# 1_Main.net
KiCad netlist of a schematic drawn in EAGLE
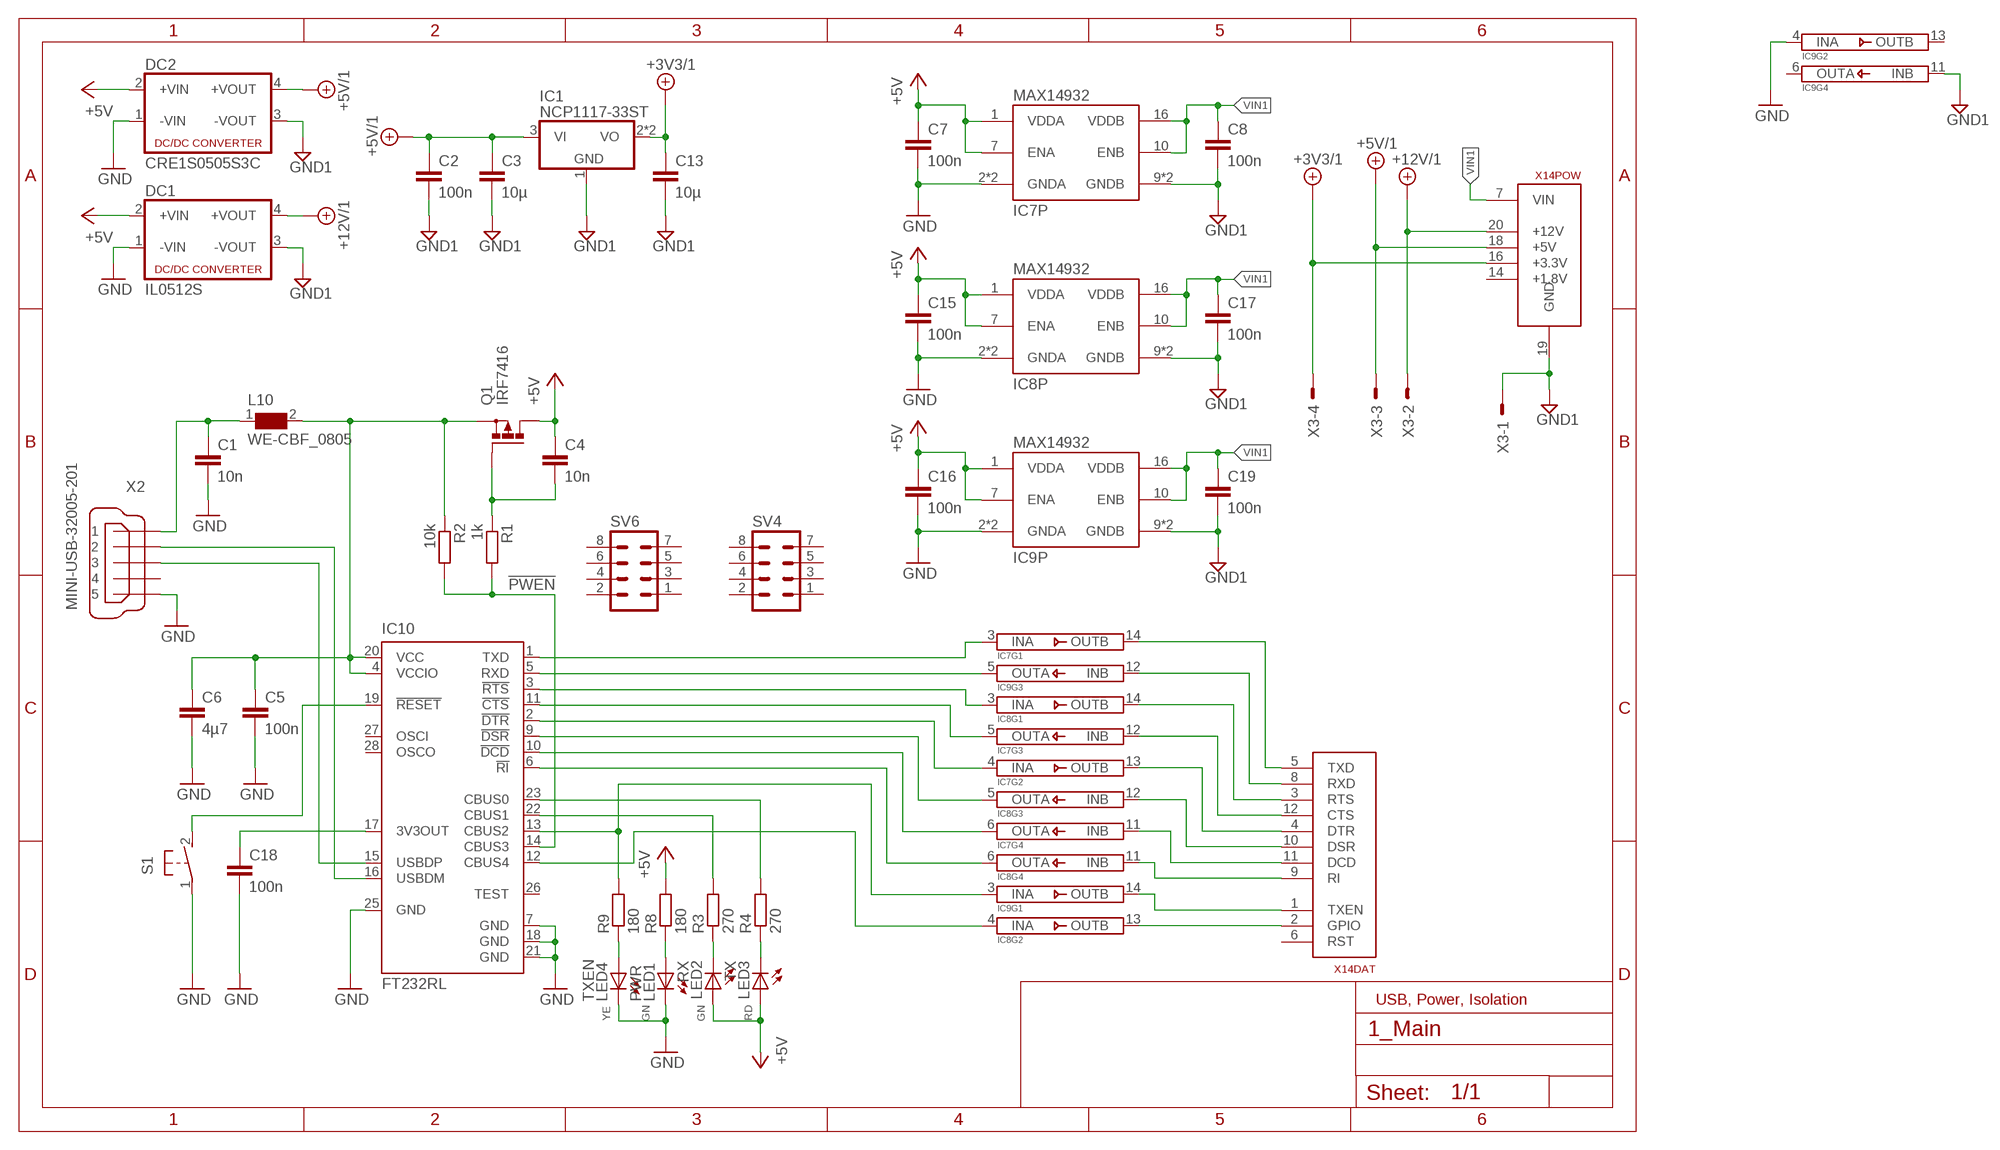
[diagram p0: schematic, sheet 1]

(export (version "E")
  (design (tool "Eeschema 10.0.6"))
  (components
    (comp (ref "C1")
      (value "10n")
      (footprint "eagle-import:C0805")
      (libsource (lib "eagle-import") (part "C-EUC0805"))
    )
    (comp (ref "C2")
      (value "100n")
      (footprint "eagle-import:C0805")
      (libsource (lib "eagle-import") (part "C-EUC0805"))
    )
    (comp (ref "C3")
      (value "10µ")
      (footprint "eagle-import:C0805")
      (libsource (lib "eagle-import") (part "C-EUC0805"))
    )
    (comp (ref "C4")
      (value "10n")
      (footprint "eagle-import:C0805")
      (libsource (lib "eagle-import") (part "C-EUC0805"))
    )
    (comp (ref "C5")
      (value "100n")
      (footprint "eagle-import:C0805")
      (libsource (lib "eagle-import") (part "C-EUC0805"))
    )
    (comp (ref "C6")
      (value "4µ7")
      (footprint "eagle-import:C0805")
      (libsource (lib "eagle-import") (part "C-EUC0805"))
    )
    (comp (ref "C7")
      (value "100n")
      (footprint "eagle-import:C0805")
      (libsource (lib "eagle-import") (part "C-EUC0805"))
    )
    (comp (ref "C8")
      (value "100n")
      (footprint "eagle-import:C0805")
      (libsource (lib "eagle-import") (part "C-EUC0805"))
    )
    (comp (ref "C13")
      (value "10µ")
      (footprint "eagle-import:C0805")
      (libsource (lib "eagle-import") (part "C-EUC0805"))
    )
    (comp (ref "C15")
      (value "100n")
      (footprint "eagle-import:C0805")
      (libsource (lib "eagle-import") (part "C-EUC0805"))
    )
    (comp (ref "C16")
      (value "100n")
      (footprint "eagle-import:C0805")
      (libsource (lib "eagle-import") (part "C-EUC0805"))
    )
    (comp (ref "C17")
      (value "100n")
      (footprint "eagle-import:C0805")
      (libsource (lib "eagle-import") (part "C-EUC0805"))
    )
    (comp (ref "C18")
      (value "100n")
      (footprint "eagle-import:C0805")
      (libsource (lib "eagle-import") (part "C-EUC0805"))
    )
    (comp (ref "C19")
      (value "100n")
      (footprint "eagle-import:C0805")
      (libsource (lib "eagle-import") (part "C-EUC0805"))
    )
    (comp (ref "DC1")
      (value "IL0512S")
      (footprint "eagle-import:NME")
      (fields (field (name "MF") "C & D TECHNOLOGIES, INC") (field (name "MPN") "NME1205D"))
      (libsource (lib "eagle-import") (part "NME"))
    )
    (comp (ref "DC2")
      (value "CRE1S0505S3C")
      (footprint "eagle-import:NME")
      (fields (field (name "MF") "C & D TECHNOLOGIES, INC") (field (name "MPN") "NME1205D"))
      (libsource (lib "eagle-import") (part "NME"))
    )
    (comp (ref "IC1")
      (value "NCP1117-33ST")
      (footprint "eagle-import:SOT223")
      (libsource (lib "eagle-import") (part "NCP1117ST-33"))
    )
    (comp (ref "IC7")
      (value "MAX14932")
      (footprint "eagle-import:SO16")
      (libsource (lib "eagle-import") (part "MAX14932"))
    )
    (comp (ref "IC8")
      (value "MAX14932")
      (footprint "eagle-import:SO16")
      (libsource (lib "eagle-import") (part "MAX14932"))
    )
    (comp (ref "IC9")
      (value "MAX14932")
      (footprint "eagle-import:SO16")
      (libsource (lib "eagle-import") (part "MAX14932"))
    )
    (comp (ref "IC10")
      (value "FT232RL")
      (footprint "eagle-import:SSOP28")
      (libsource (lib "eagle-import") (part "FT232RL"))
    )
    (comp (ref "L10")
      (value "WE-CBF_0805")
      (footprint "eagle-import:0805")
      (libsource (lib "eagle-import") (part "WE-CBF_0805"))
    )
    (comp (ref "LED1")
      (value "PWR")
      (footprint "eagle-import:CHIPLED_0603")
      (fields (field (name "COLOR") "GN"))
      (libsource (lib "eagle-import") (part "LEDCHIPLED_0603"))
    )
    (comp (ref "LED2")
      (value "RX")
      (footprint "eagle-import:CHIPLED_0603")
      (fields (field (name "COLOR") "GN"))
      (libsource (lib "eagle-import") (part "LEDCHIPLED_0603"))
    )
    (comp (ref "LED3")
      (value "TX")
      (footprint "eagle-import:CHIPLED_0603")
      (fields (field (name "COLOR") "RD"))
      (libsource (lib "eagle-import") (part "LEDCHIPLED_0603"))
    )
    (comp (ref "LED4")
      (value "TXEN")
      (footprint "eagle-import:CHIPLED_0603")
      (fields (field (name "COLOR") "YE"))
      (libsource (lib "eagle-import") (part "LEDCHIPLED_0603"))
    )
    (comp (ref "Q1")
      (value "IRF7416")
      (footprint "eagle-import:SO-08")
      (libsource (lib "eagle-import") (part "P-MOSFET-SO8"))
    )
    (comp (ref "R1")
      (value "1k")
      (footprint "eagle-import:R0805")
      (libsource (lib "eagle-import") (part "R-EU_R0805"))
    )
    (comp (ref "R2")
      (value "10k")
      (footprint "eagle-import:R0805")
      (libsource (lib "eagle-import") (part "R-EU_R0805"))
    )
    (comp (ref "R3")
      (value "270")
      (footprint "eagle-import:R0805")
      (libsource (lib "eagle-import") (part "R-EU_R0805"))
    )
    (comp (ref "R4")
      (value "270")
      (footprint "eagle-import:R0805")
      (libsource (lib "eagle-import") (part "R-EU_R0805"))
    )
    (comp (ref "R8")
      (value "180")
      (footprint "eagle-import:R0805")
      (libsource (lib "eagle-import") (part "R-EU_R0805"))
    )
    (comp (ref "R9")
      (value "180")
      (footprint "eagle-import:R0805")
      (libsource (lib "eagle-import") (part "R-EU_R0805"))
    )
    (comp (ref "S1")
      (value "31-XX")
      (footprint "eagle-import:B3F-31XX")
      (fields (field (name "MPN") "B3F-3100"))
      (libsource (lib "eagle-import") (part "31-XX"))
    )
    (comp (ref "SV4")
      (value "MA04-2")
      (footprint "eagle-import:MA04-2")
      (libsource (lib "eagle-import") (part "MA04-2"))
    )
    (comp (ref "SV6")
      (value "MA04-2")
      (footprint "eagle-import:MA04-2")
      (libsource (lib "eagle-import") (part "MA04-2"))
    )
    (comp (ref "X2")
      (value "MINI-USB-32005-201")
      (footprint "eagle-import:32005-201")
      (libsource (lib "eagle-import") (part "MINI-USB-32005-201"))
    )
    (comp (ref "X3")
      (value "AKL18X-04W")
      (footprint "eagle-import:AKL182-04")
      (libsource (lib "eagle-import") (part "AKL18X-04W"))
    )
    (comp (ref "X14")
      (value "ALLSERIALMM")
      (footprint "eagle-import:MAIN-THT")
      (libsource (lib "eagle-import") (part "ALLSERIALMM"))
    )
  )
  (nets
    (net (code "1") (name "+3V3{slash}1") (class "Default")
      (node (ref "C13") (pin "1") (pinfunction "1_1") (pintype "passive"))
      (node (ref "IC1") (pin "2") (pinfunction "VO_2") (pintype "passive"))
      (node (ref "IC1") (pin "4") (pinfunction "VO_4") (pintype "passive"))
      (node (ref "X14") (pin "16") (pinfunction "+3.3V_16") (pintype "bidirectional"))
      (node (ref "X3") (pin "P$4") (pinfunction "S_P$4") (pintype "passive"))
    )
    (net (code "2") (name "+5V") (class "Default")
      (node (ref "C15") (pin "1") (pinfunction "1_1") (pintype "passive"))
      (node (ref "C16") (pin "1") (pinfunction "1_1") (pintype "passive"))
      (node (ref "C4") (pin "1") (pinfunction "1_1") (pintype "passive"))
      (node (ref "C7") (pin "1") (pinfunction "1_1") (pintype "passive"))
      (node (ref "DC1") (pin "2") (pinfunction "+VIN_2") (pintype "passive"))
      (node (ref "DC2") (pin "2") (pinfunction "+VIN_2") (pintype "passive"))
      (node (ref "IC7") (pin "1") (pinfunction "VDDA_1") (pintype "power_in"))
      (node (ref "IC7") (pin "7") (pinfunction "ENA_7") (pintype "input"))
      (node (ref "IC8") (pin "1") (pinfunction "VDDA_1") (pintype "power_in"))
      (node (ref "IC8") (pin "7") (pinfunction "ENA_7") (pintype "input"))
      (node (ref "IC9") (pin "1") (pinfunction "VDDA_1") (pintype "power_in"))
      (node (ref "IC9") (pin "7") (pinfunction "ENA_7") (pintype "input"))
      (node (ref "LED2") (pin "A") (pinfunction "A_A") (pintype "passive"))
      (node (ref "LED3") (pin "A") (pinfunction "A_A") (pintype "passive"))
      (node (ref "Q1") (pin "5") (pinfunction "D_5") (pintype "passive"))
      (node (ref "Q1") (pin "6") (pinfunction "D_6") (pintype "passive"))
      (node (ref "Q1") (pin "7") (pinfunction "D_7") (pintype "passive"))
      (node (ref "Q1") (pin "8") (pinfunction "D_8") (pintype "passive"))
      (node (ref "R8") (pin "2") (pinfunction "2_2") (pintype "passive"))
    )
    (net (code "3") (name "+5V{slash}1") (class "Default")
      (node (ref "C2") (pin "1") (pinfunction "1_1") (pintype "passive"))
      (node (ref "C3") (pin "1") (pinfunction "1_1") (pintype "passive"))
      (node (ref "DC2") (pin "4") (pinfunction "+VOUT_4") (pintype "passive"))
      (node (ref "IC1") (pin "3") (pinfunction "VI_3") (pintype "input"))
      (node (ref "X14") (pin "18") (pinfunction "+5V_18") (pintype "bidirectional"))
      (node (ref "X3") (pin "P$3") (pinfunction "S_P$3") (pintype "passive"))
    )
    (net (code "4") (name "+12V{slash}1") (class "Default")
      (node (ref "DC1") (pin "4") (pinfunction "+VOUT_4") (pintype "passive"))
      (node (ref "X14") (pin "20") (pinfunction "+12V_20") (pintype "bidirectional"))
      (node (ref "X3") (pin "P$2") (pinfunction "S_P$2") (pintype "passive"))
    )
    (net (code "5") (name "/~{PWEN}") (class "Default")
      (node (ref "IC10") (pin "14") (pinfunction "CBUS3_14") (pintype "bidirectional"))
      (node (ref "R1") (pin "2") (pinfunction "2_2") (pintype "passive"))
      (node (ref "R2") (pin "2") (pinfunction "2_2") (pintype "passive"))
    )
    (net (code "6") (name "GND") (class "Default")
      (node (ref "C1") (pin "2") (pinfunction "2_2") (pintype "passive"))
      (node (ref "C15") (pin "2") (pinfunction "2_2") (pintype "passive"))
      (node (ref "C16") (pin "2") (pinfunction "2_2") (pintype "passive"))
      (node (ref "C18") (pin "2") (pinfunction "2_2") (pintype "passive"))
      (node (ref "C5") (pin "2") (pinfunction "2_2") (pintype "passive"))
      (node (ref "C6") (pin "2") (pinfunction "2_2") (pintype "passive"))
      (node (ref "C7") (pin "2") (pinfunction "2_2") (pintype "passive"))
      (node (ref "DC1") (pin "1") (pinfunction "-VIN_1") (pintype "passive"))
      (node (ref "DC2") (pin "1") (pinfunction "-VIN_1") (pintype "passive"))
      (node (ref "IC10") (pin "18") (pinfunction "GND_18") (pintype "power_in"))
      (node (ref "IC10") (pin "21") (pinfunction "GND_21") (pintype "power_in"))
      (node (ref "IC10") (pin "25") (pinfunction "GND_25") (pintype "power_in"))
      (node (ref "IC10") (pin "7") (pinfunction "GND_7") (pintype "power_in"))
      (node (ref "IC7") (pin "2") (pinfunction "GNDA_2") (pintype "power_in"))
      (node (ref "IC7") (pin "8") (pinfunction "GNDA_8") (pintype "power_in"))
      (node (ref "IC8") (pin "2") (pinfunction "GNDA_2") (pintype "power_in"))
      (node (ref "IC8") (pin "8") (pinfunction "GNDA_8") (pintype "power_in"))
      (node (ref "IC9") (pin "2") (pinfunction "GNDA_2") (pintype "power_in"))
      (node (ref "IC9") (pin "4") (pinfunction "INA_4") (pintype "input"))
      (node (ref "IC9") (pin "8") (pinfunction "GNDA_8") (pintype "power_in"))
      (node (ref "LED1") (pin "C") (pinfunction "C_C") (pintype "passive"))
      (node (ref "LED4") (pin "C") (pinfunction "C_C") (pintype "passive"))
      (node (ref "S1") (pin "1") (pinfunction "P_1") (pintype "passive"))
      (node (ref "X2") (pin "5") (pinfunction "5_5") (pintype "passive"))
    )
    (net (code "7") (name "GND1") (class "Default")
      (node (ref "C13") (pin "2") (pinfunction "2_2") (pintype "passive"))
      (node (ref "C17") (pin "2") (pinfunction "2_2") (pintype "passive"))
      (node (ref "C19") (pin "2") (pinfunction "2_2") (pintype "passive"))
      (node (ref "C2") (pin "2") (pinfunction "2_2") (pintype "passive"))
      (node (ref "C3") (pin "2") (pinfunction "2_2") (pintype "passive"))
      (node (ref "C8") (pin "2") (pinfunction "2_2") (pintype "passive"))
      (node (ref "DC1") (pin "3") (pinfunction "-VOUT_3") (pintype "passive"))
      (node (ref "DC2") (pin "3") (pinfunction "-VOUT_3") (pintype "passive"))
      (node (ref "IC1") (pin "1") (pinfunction "GND_1") (pintype "passive"))
      (node (ref "IC7") (pin "15") (pinfunction "GNDB_15") (pintype "power_in"))
      (node (ref "IC7") (pin "9") (pinfunction "GNDB_9") (pintype "power_in"))
      (node (ref "IC8") (pin "15") (pinfunction "GNDB_15") (pintype "power_in"))
      (node (ref "IC8") (pin "9") (pinfunction "GNDB_9") (pintype "power_in"))
      (node (ref "IC9") (pin "11") (pinfunction "INB_11") (pintype "input"))
      (node (ref "IC9") (pin "15") (pinfunction "GNDB_15") (pintype "power_in"))
      (node (ref "IC9") (pin "9") (pinfunction "GNDB_9") (pintype "power_in"))
      (node (ref "X14") (pin "19") (pinfunction "GND_19") (pintype "bidirectional"))
      (node (ref "X3") (pin "P$1") (pinfunction "S_P$1") (pintype "passive"))
    )
    (net (code "8") (name "Net-(C1-Pad1)") (class "Default")
      (node (ref "C1") (pin "1") (pinfunction "1_1") (pintype "passive"))
      (node (ref "L10") (pin "1") (pinfunction "1_1") (pintype "passive"))
      (node (ref "X2") (pin "1") (pinfunction "1_1") (pintype "passive"))
    )
    (net (code "9") (name "Net-(IC7A-OUTB)") (class "Default")
      (node (ref "IC7") (pin "14") (pinfunction "OUTB_14") (pintype "output"))
      (node (ref "X14") (pin "5") (pinfunction "TXD_5") (pintype "bidirectional"))
    )
    (net (code "10") (name "Net-(IC7B-OUTB)") (class "Default")
      (node (ref "IC7") (pin "13") (pinfunction "OUTB_13") (pintype "output"))
      (node (ref "X14") (pin "4") (pinfunction "DTR_4") (pintype "bidirectional"))
    )
    (net (code "11") (name "Net-(IC7C-INB)") (class "Default")
      (node (ref "IC7") (pin "12") (pinfunction "INB_12") (pintype "input"))
      (node (ref "X14") (pin "12") (pinfunction "CTS_12") (pintype "bidirectional"))
    )
    (net (code "12") (name "Net-(IC7D-INB)") (class "Default")
      (node (ref "IC7") (pin "11") (pinfunction "INB_11") (pintype "input"))
      (node (ref "X14") (pin "11") (pinfunction "DCD_11") (pintype "bidirectional"))
    )
    (net (code "13") (name "Net-(IC8A-OUTB)") (class "Default")
      (node (ref "IC8") (pin "14") (pinfunction "OUTB_14") (pintype "output"))
      (node (ref "X14") (pin "3") (pinfunction "RTS_3") (pintype "bidirectional"))
    )
    (net (code "14") (name "Net-(IC8B-OUTB)") (class "Default")
      (node (ref "IC8") (pin "13") (pinfunction "OUTB_13") (pintype "output"))
      (node (ref "X14") (pin "2") (pinfunction "GPIO_2") (pintype "bidirectional"))
    )
    (net (code "15") (name "Net-(IC8C-INB)") (class "Default")
      (node (ref "IC8") (pin "12") (pinfunction "INB_12") (pintype "input"))
      (node (ref "X14") (pin "10") (pinfunction "DSR_10") (pintype "bidirectional"))
    )
    (net (code "16") (name "Net-(IC8D-INB)") (class "Default")
      (node (ref "IC8") (pin "11") (pinfunction "INB_11") (pintype "input"))
      (node (ref "X14") (pin "9") (pinfunction "RI_9") (pintype "bidirectional"))
    )
    (net (code "17") (name "Net-(IC9A-OUTB)") (class "Default")
      (node (ref "IC9") (pin "14") (pinfunction "OUTB_14") (pintype "output"))
      (node (ref "X14") (pin "1") (pinfunction "TXEN_1") (pintype "bidirectional"))
    )
    (net (code "18") (name "Net-(IC9C-INB)") (class "Default")
      (node (ref "IC9") (pin "12") (pinfunction "INB_12") (pintype "input"))
      (node (ref "X14") (pin "8") (pinfunction "RXD_8") (pintype "bidirectional"))
    )
    (net (code "19") (name "Net-(IC10-3V3OUT)") (class "Default")
      (node (ref "C18") (pin "1") (pinfunction "1_1") (pintype "passive"))
      (node (ref "IC10") (pin "17") (pinfunction "3V3OUT_17") (pintype "output"))
    )
    (net (code "20") (name "Net-(IC10-CBUS0)") (class "Default")
      (node (ref "IC10") (pin "23") (pinfunction "CBUS0_23") (pintype "bidirectional"))
      (node (ref "R4") (pin "2") (pinfunction "2_2") (pintype "passive"))
    )
    (net (code "21") (name "Net-(IC10-CBUS1)") (class "Default")
      (node (ref "IC10") (pin "22") (pinfunction "CBUS1_22") (pintype "bidirectional"))
      (node (ref "R3") (pin "2") (pinfunction "2_2") (pintype "passive"))
    )
    (net (code "22") (name "Net-(IC10-CBUS2)") (class "Default")
      (node (ref "IC10") (pin "13") (pinfunction "CBUS2_13") (pintype "bidirectional"))
      (node (ref "IC9") (pin "3") (pinfunction "INA_3") (pintype "input"))
      (node (ref "R9") (pin "2") (pinfunction "2_2") (pintype "passive"))
    )
    (net (code "23") (name "Net-(IC10-CBUS4)") (class "Default")
      (node (ref "IC10") (pin "12") (pinfunction "CBUS4_12") (pintype "bidirectional"))
      (node (ref "IC8") (pin "4") (pinfunction "INA_4") (pintype "input"))
    )
    (net (code "24") (name "Net-(IC10-RXD)") (class "Default")
      (node (ref "IC10") (pin "5") (pinfunction "RXD_5") (pintype "input"))
      (node (ref "IC9") (pin "5") (pinfunction "OUTA_5") (pintype "output"))
    )
    (net (code "25") (name "Net-(IC10-TXD)") (class "Default")
      (node (ref "IC10") (pin "1") (pinfunction "TXD_1") (pintype "output"))
      (node (ref "IC7") (pin "3") (pinfunction "INA_3") (pintype "input"))
    )
    (net (code "26") (name "Net-(IC10-USBDM)") (class "Default")
      (node (ref "IC10") (pin "16") (pinfunction "USBDM_16") (pintype "bidirectional"))
      (node (ref "X2") (pin "2") (pinfunction "2_2") (pintype "passive"))
    )
    (net (code "27") (name "Net-(IC10-USBDP)") (class "Default")
      (node (ref "IC10") (pin "15") (pinfunction "USBDP_15") (pintype "bidirectional"))
      (node (ref "X2") (pin "3") (pinfunction "3_3") (pintype "passive"))
    )
    (net (code "28") (name "Net-(IC10-VCC)") (class "Default")
      (node (ref "C5") (pin "1") (pinfunction "1_1") (pintype "passive"))
      (node (ref "C6") (pin "1") (pinfunction "1_1") (pintype "passive"))
      (node (ref "IC10") (pin "20") (pinfunction "VCC_20") (pintype "power_in"))
      (node (ref "IC10") (pin "4") (pinfunction "VCCIO_4") (pintype "power_in"))
      (node (ref "L10") (pin "2") (pinfunction "2_2") (pintype "passive"))
      (node (ref "Q1") (pin "1") (pinfunction "S_1") (pintype "passive"))
      (node (ref "Q1") (pin "2") (pinfunction "S_2") (pintype "passive"))
      (node (ref "Q1") (pin "3") (pinfunction "S_3") (pintype "passive"))
      (node (ref "R2") (pin "1") (pinfunction "1_1") (pintype "passive"))
    )
    (net (code "29") (name "Net-(IC10-~{CTS})") (class "Default")
      (node (ref "IC10") (pin "11") (pinfunction "~{CTS}_11") (pintype "input"))
      (node (ref "IC7") (pin "5") (pinfunction "OUTA_5") (pintype "output"))
    )
    (net (code "30") (name "Net-(IC10-~{DCD})") (class "Default")
      (node (ref "IC10") (pin "10") (pinfunction "~{DCD}_10") (pintype "input"))
      (node (ref "IC7") (pin "6") (pinfunction "OUTA_6") (pintype "output"))
    )
    (net (code "31") (name "Net-(IC10-~{DSR})") (class "Default")
      (node (ref "IC10") (pin "9") (pinfunction "~{DSR}_9") (pintype "input"))
      (node (ref "IC8") (pin "5") (pinfunction "OUTA_5") (pintype "output"))
    )
    (net (code "32") (name "Net-(IC10-~{DTR})") (class "Default")
      (node (ref "IC10") (pin "2") (pinfunction "~{DTR}_2") (pintype "output"))
      (node (ref "IC7") (pin "4") (pinfunction "INA_4") (pintype "input"))
    )
    (net (code "33") (name "Net-(IC10-~{RESET})") (class "Default")
      (node (ref "IC10") (pin "19") (pinfunction "~{RESET}_19") (pintype "input"))
      (node (ref "S1") (pin "2") (pinfunction "S_2") (pintype "passive"))
    )
    (net (code "34") (name "Net-(IC10-~{RI})") (class "Default")
      (node (ref "IC10") (pin "6") (pinfunction "~{RI}_6") (pintype "input"))
      (node (ref "IC8") (pin "6") (pinfunction "OUTA_6") (pintype "output"))
    )
    (net (code "35") (name "Net-(IC10-~{RTS})") (class "Default")
      (node (ref "IC10") (pin "3") (pinfunction "~{RTS}_3") (pintype "output"))
      (node (ref "IC8") (pin "3") (pinfunction "INA_3") (pintype "input"))
    )
    (net (code "36") (name "Net-(LED1-PadA)") (class "Default")
      (node (ref "LED1") (pin "A") (pinfunction "A_A") (pintype "passive"))
      (node (ref "R8") (pin "1") (pinfunction "1_1") (pintype "passive"))
    )
    (net (code "37") (name "Net-(LED2-PadC)") (class "Default")
      (node (ref "LED2") (pin "C") (pinfunction "C_C") (pintype "passive"))
      (node (ref "R3") (pin "1") (pinfunction "1_1") (pintype "passive"))
    )
    (net (code "38") (name "Net-(LED3-PadC)") (class "Default")
      (node (ref "LED3") (pin "C") (pinfunction "C_C") (pintype "passive"))
      (node (ref "R4") (pin "1") (pinfunction "1_1") (pintype "passive"))
    )
    (net (code "39") (name "Net-(LED4-PadA)") (class "Default")
      (node (ref "LED4") (pin "A") (pinfunction "A_A") (pintype "passive"))
      (node (ref "R9") (pin "1") (pinfunction "1_1") (pintype "passive"))
    )
    (net (code "40") (name "Net-(Q1-G)") (class "Default")
      (node (ref "C4") (pin "2") (pinfunction "2_2") (pintype "passive"))
      (node (ref "Q1") (pin "4") (pinfunction "G_4") (pintype "passive"))
      (node (ref "R1") (pin "1") (pinfunction "1_1") (pintype "passive"))
    )
    (net (code "41") (name "VIN1") (class "Default")
      (node (ref "C17") (pin "1") (pinfunction "1_1") (pintype "passive"))
      (node (ref "C19") (pin "1") (pinfunction "1_1") (pintype "passive"))
      (node (ref "C8") (pin "1") (pinfunction "1_1") (pintype "passive"))
      (node (ref "IC7") (pin "10") (pinfunction "ENB_10") (pintype "input"))
      (node (ref "IC7") (pin "16") (pinfunction "VDDB_16") (pintype "power_in"))
      (node (ref "IC8") (pin "10") (pinfunction "ENB_10") (pintype "input"))
      (node (ref "IC8") (pin "16") (pinfunction "VDDB_16") (pintype "power_in"))
      (node (ref "IC9") (pin "10") (pinfunction "ENB_10") (pintype "input"))
      (node (ref "IC9") (pin "16") (pinfunction "VDDB_16") (pintype "power_in"))
      (node (ref "X14") (pin "7") (pinfunction "VIN_7") (pintype "bidirectional"))
    )
    (net (code "42") (name "unconnected-(IC9B-OUTB-Pad13)") (class "Default")
      (node (ref "IC9") (pin "13") (pinfunction "OUTB_13") (pintype "output"))
    )
    (net (code "43") (name "unconnected-(IC9D-OUTA-Pad6)") (class "Default")
      (node (ref "IC9") (pin "6") (pinfunction "OUTA_6") (pintype "output"))
    )
    (net (code "44") (name "unconnected-(IC10-OSCI-Pad27)") (class "Default")
      (node (ref "IC10") (pin "27") (pinfunction "OSCI_27") (pintype "input"))
    )
    (net (code "45") (name "unconnected-(IC10-OSCO-Pad28)") (class "Default")
      (node (ref "IC10") (pin "28") (pinfunction "OSCO_28") (pintype "output"))
    )
    (net (code "46") (name "unconnected-(IC10-TEST-Pad26)") (class "Default")
      (node (ref "IC10") (pin "26") (pinfunction "TEST_26") (pintype "input"))
    )
    (net (code "47") (name "unconnected-(SV4-Pad1)") (class "Default")
      (node (ref "SV4") (pin "1") (pinfunction "1_1") (pintype "passive"))
    )
    (net (code "48") (name "unconnected-(SV4-Pad2)") (class "Default")
      (node (ref "SV4") (pin "2") (pinfunction "2_2") (pintype "passive"))
    )
    (net (code "49") (name "unconnected-(SV4-Pad3)") (class "Default")
      (node (ref "SV4") (pin "3") (pinfunction "3_3") (pintype "passive"))
    )
    (net (code "50") (name "unconnected-(SV4-Pad4)") (class "Default")
      (node (ref "SV4") (pin "4") (pinfunction "4_4") (pintype "passive"))
    )
    (net (code "51") (name "unconnected-(SV4-Pad5)") (class "Default")
      (node (ref "SV4") (pin "5") (pinfunction "5_5") (pintype "passive"))
    )
    (net (code "52") (name "unconnected-(SV4-Pad6)") (class "Default")
      (node (ref "SV4") (pin "6") (pinfunction "6_6") (pintype "passive"))
    )
    (net (code "53") (name "unconnected-(SV4-Pad7)") (class "Default")
      (node (ref "SV4") (pin "7") (pinfunction "7_7") (pintype "passive"))
    )
    (net (code "54") (name "unconnected-(SV4-Pad8)") (class "Default")
      (node (ref "SV4") (pin "8") (pinfunction "8_8") (pintype "passive"))
    )
    (net (code "55") (name "unconnected-(SV6-Pad1)") (class "Default")
      (node (ref "SV6") (pin "1") (pinfunction "1_1") (pintype "passive"))
    )
    (net (code "56") (name "unconnected-(SV6-Pad2)") (class "Default")
      (node (ref "SV6") (pin "2") (pinfunction "2_2") (pintype "passive"))
    )
    (net (code "57") (name "unconnected-(SV6-Pad3)") (class "Default")
      (node (ref "SV6") (pin "3") (pinfunction "3_3") (pintype "passive"))
    )
    (net (code "58") (name "unconnected-(SV6-Pad4)") (class "Default")
      (node (ref "SV6") (pin "4") (pinfunction "4_4") (pintype "passive"))
    )
    (net (code "59") (name "unconnected-(SV6-Pad5)") (class "Default")
      (node (ref "SV6") (pin "5") (pinfunction "5_5") (pintype "passive"))
    )
    (net (code "60") (name "unconnected-(SV6-Pad6)") (class "Default")
      (node (ref "SV6") (pin "6") (pinfunction "6_6") (pintype "passive"))
    )
    (net (code "61") (name "unconnected-(SV6-Pad7)") (class "Default")
      (node (ref "SV6") (pin "7") (pinfunction "7_7") (pintype "passive"))
    )
    (net (code "62") (name "unconnected-(SV6-Pad8)") (class "Default")
      (node (ref "SV6") (pin "8") (pinfunction "8_8") (pintype "passive"))
    )
    (net (code "63") (name "unconnected-(X2-Pad4)") (class "Default")
      (node (ref "X2") (pin "4") (pinfunction "4_4") (pintype "passive"))
    )
    (net (code "64") (name "unconnected-(X14A-RST-Pad6)") (class "Default")
      (node (ref "X14") (pin "6") (pinfunction "RST_6") (pintype "bidirectional"))
    )
    (net (code "65") (name "unconnected-(X14B-+1.8V-Pad14)") (class "Default")
      (node (ref "X14") (pin "14") (pinfunction "+1.8V_14") (pintype "bidirectional"))
    )
  )
)
